# shematic.net
KiCad netlist of a schematic drawn in Altium Designer
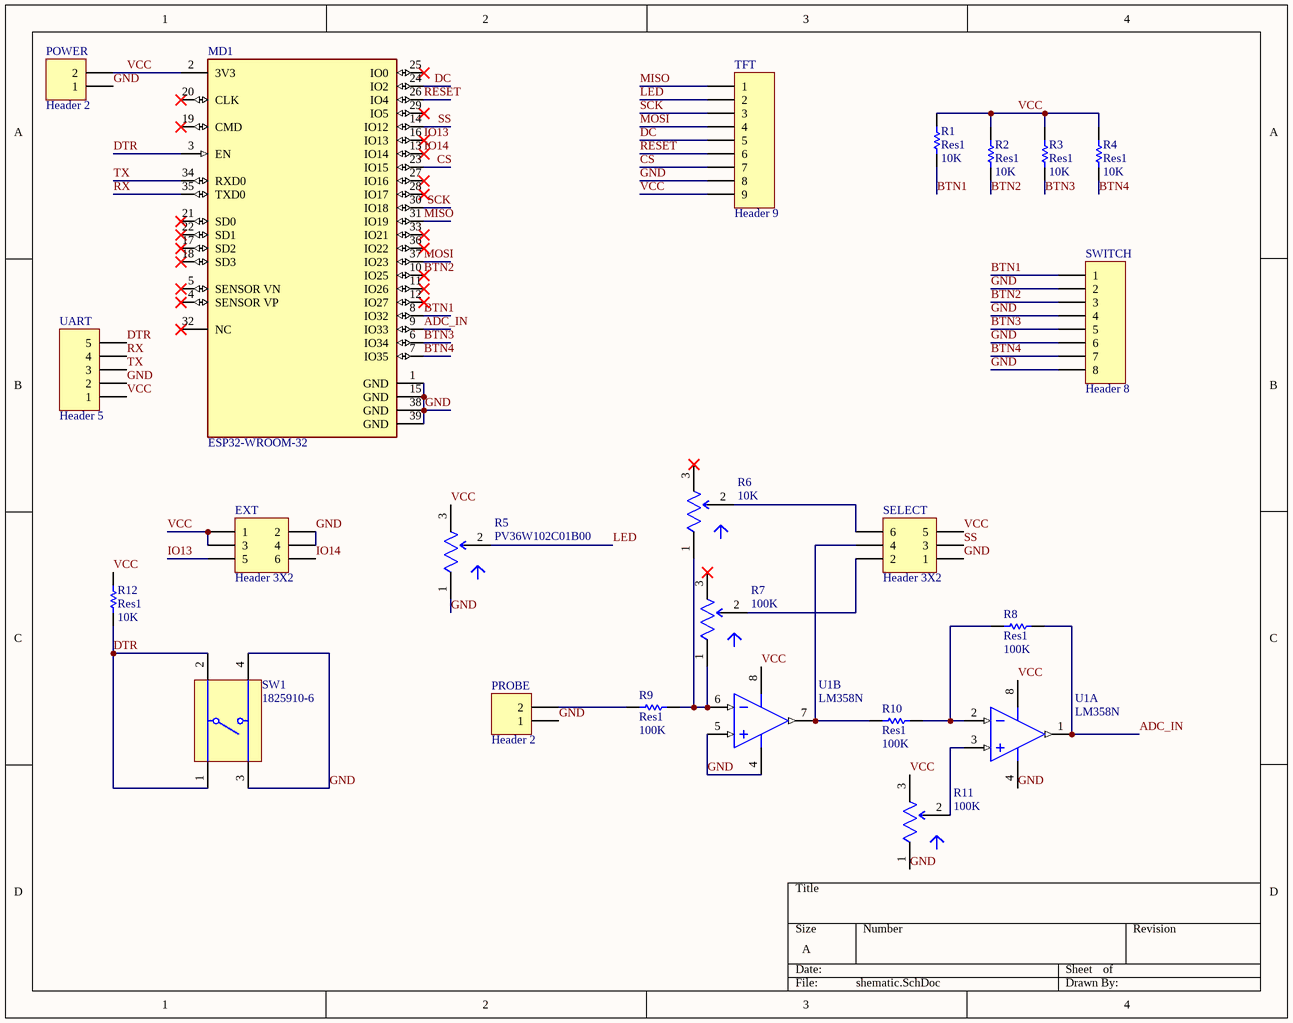
[diagram p0: shematic.SchDoc]

(export (version "E")
  (design (tool "Eeschema 10.0.6"))
  (components
    (comp (ref "EXT")
      (value "Header 3X2")
      (footprint "HDR2X3")
      (description "Header, 3-Pin, Dual row")
      (fields (field (name "PUBLISHER") "Altium Limited"))
      (libsource (lib "") (part "Header 3X2_1"))
    )
    (comp (ref "MD1")
      (value "ESP32-WROOM-32")
      (footprint "FP-ESP32-WROOM-32-MFG")
      (description "RX TXRX MOD WIFI SURFACE MOUNT")
      (libsource (lib "Altium Content Vault") (part "ee866abf0b6c51247b7f5cdebf2f250"))
    )
    (comp (ref "POWER")
      (value "Header 2")
      (footprint "HDR1X2")
      (description "Header, 2-Pin")
      (fields (field (name "PUBLISHER") "Altium Limited"))
      (libsource (lib "Miscellaneous Connectors") (part "Header 2"))
    )
    (comp (ref "PROBE")
      (value "Header 2")
      (footprint "HDR1X2")
      (description "Header, 2-Pin")
      (fields (field (name "PUBLISHER") "Altium Limited"))
      (libsource (lib "Miscellaneous Connectors") (part "Header 2"))
    )
    (comp (ref "R1")
      (value "Res1")
      (footprint "AXIAL-0.3")
      (description "Resistor")
      (fields (field (name "ALTIUM_VALUE") "10K") (field (name "PUBLISHER") "Altium Limited"))
      (libsource (lib "Miscellaneous Devices") (part "Res1"))
    )
    (comp (ref "R2")
      (value "Res1")
      (footprint "AXIAL-0.3")
      (description "Resistor")
      (fields (field (name "ALTIUM_VALUE") "10K") (field (name "PUBLISHER") "Altium Limited"))
      (libsource (lib "Miscellaneous Devices") (part "Res1"))
    )
    (comp (ref "R3")
      (value "Res1")
      (footprint "AXIAL-0.3")
      (description "Resistor")
      (fields (field (name "ALTIUM_VALUE") "10K") (field (name "PUBLISHER") "Altium Limited"))
      (libsource (lib "Miscellaneous Devices") (part "Res1"))
    )
    (comp (ref "R4")
      (value "Res1")
      (footprint "AXIAL-0.3")
      (description "Resistor")
      (fields (field (name "ALTIUM_VALUE") "10K") (field (name "PUBLISHER") "Altium Limited"))
      (libsource (lib "Miscellaneous Devices") (part "Res1"))
    )
    (comp (ref "R5")
      (value "PV36W102C01B00")
      (footprint "FP-PV36W-MFG")
      (description "TRIMMER 1K OHM 0.5W PC PIN TOP")
      (fields
        (field (name "OCTOPART") "https://octopart.com/pv36w102c01b00-bourns-71612321")
        (field (name "TOLERANCE") "10%")
      )
      (libsource (lib "Altium Content Vault") (part "3b5a993e1b8b55ba5d1e0805a406c64"))
    )
    (comp (ref "R6")
      (value "10K")
      (footprint "FP-PV36W-MFG")
      (description "TRIMMER 1K OHM 0.5W PC PIN TOP")
      (fields
        (field (name "OCTOPART") "https://octopart.com/pv36w102c01b00-bourns-71612321")
        (field (name "MANUFACTURER PART NUMBER") "PV36W102C01B00")
      )
      (libsource (lib "Altium Content Vault") (part "3b5a993e1b8b55ba5d1e0805a406c64"))
    )
    (comp (ref "R7")
      (value "100K")
      (footprint "FP-PV36W-MFG")
      (description "TRIMMER 1K OHM 0.5W PC PIN TOP")
      (fields
        (field (name "OCTOPART") "https://octopart.com/pv36w102c01b00-bourns-71612321")
        (field (name "MANUFACTURER PART NUMBER") "PV36W102C01B00")
      )
      (libsource (lib "Altium Content Vault") (part "3b5a993e1b8b55ba5d1e0805a406c64"))
    )
    (comp (ref "R8")
      (value "Res1")
      (footprint "AXIAL-0.3")
      (description "Resistor")
      (fields (field (name "ALTIUM_VALUE") "100K") (field (name "PUBLISHER") "Altium Limited"))
      (libsource (lib "Miscellaneous Devices") (part "Res1"))
    )
    (comp (ref "R9")
      (value "Res1")
      (footprint "AXIAL-0.3")
      (description "Resistor")
      (fields (field (name "ALTIUM_VALUE") "100K") (field (name "PUBLISHER") "Altium Limited"))
      (libsource (lib "Miscellaneous Devices") (part "Res1"))
    )
    (comp (ref "R10")
      (value "Res1")
      (footprint "AXIAL-0.3")
      (description "Resistor")
      (fields (field (name "ALTIUM_VALUE") "100K") (field (name "PUBLISHER") "Altium Limited"))
      (libsource (lib "Miscellaneous Devices") (part "Res1"))
    )
    (comp (ref "R11")
      (value "100K")
      (footprint "FP-PV36W-MFG")
      (description "TRIMMER 1K OHM 0.5W PC PIN TOP")
      (fields
        (field (name "OCTOPART") "https://octopart.com/pv36w102c01b00-bourns-71612321")
        (field (name "MANUFACTURER PART NUMBER") "PV36W102C01B00")
      )
      (libsource (lib "Altium Content Vault") (part "3b5a993e1b8b55ba5d1e0805a406c64"))
    )
    (comp (ref "R12")
      (value "Res1")
      (footprint "AXIAL-0.3")
      (description "Resistor")
      (fields (field (name "ALTIUM_VALUE") "10K") (field (name "PUBLISHER") "Altium Limited"))
      (libsource (lib "Miscellaneous Devices") (part "Res1"))
    )
    (comp (ref "SELECT")
      (value "Header 3X2")
      (footprint "HDR2X3")
      (description "Header, 3-Pin, Dual row")
      (fields (field (name "PUBLISHER") "Altium Limited"))
      (libsource (lib "Miscellaneous Connectors") (part "Header 3X2"))
    )
    (comp (ref "SW1")
      (value "1825910-6")
      (footprint "TECO-1825910-6_V")
      (description "Tact Switch, SPST-NO, 0.05 A, -35 to 85 degC, 4-Pin THD, RoHS, Bulk")
      (fields (field (name "MANUFACTURER") "TE Connectivity"))
      (libsource (lib "Altium Content Vault") (part "SW-SPST-4_A"))
    )
    (comp (ref "SWITCH")
      (value "Header 8")
      (footprint "HDR1X8")
      (description "Header, 8-Pin")
      (fields (field (name "PUBLISHER") "Altium Limited"))
      (libsource (lib "Miscellaneous Connectors") (part "Header 8"))
    )
    (comp (ref "TFT")
      (value "Header 9")
      (footprint "HDR1X9")
      (description "Header, 9-Pin")
      (fields (field (name "PUBLISHER") "Altium Limited"))
      (libsource (lib "Miscellaneous Connectors") (part "Header 9"))
    )
    (comp (ref "U1")
      (value "LM358N")
      (footprint "ONSC-PDIP-8-626-05_M")
      (description "Single Supply Dual Operational Amplifier, 3 to 32 V, 0 to 70 degC, 8-Pin PDIP, Tube")
      (fields (field (name "MANUFACTURER") "On Semiconductor"))
      (libsource (lib "Altium Content Vault") (part "ONSC-LM358_NCV2904-8"))
    )
    (comp (ref "UART")
      (value "Header 5")
      (footprint "HDR1X5")
      (description "Header, 5-Pin")
      (fields (field (name "PUBLISHER") "Altium Limited"))
      (libsource (lib "Miscellaneous Connectors") (part "Header 5"))
    )
  )
  (nets
    (net (code "1") (name "/ADC_IN") (class "Default")
      (node (ref "MD1") (pin "9") (pinfunction "IO33_9") (pintype "bidirectional"))
      (node (ref "R8") (pin "1") (pinfunction "1_1") (pintype "passive"))
      (node (ref "U1") (pin "1") (pinfunction "OUTA_1") (pintype "output"))
    )
    (net (code "2") (name "/BTN1") (class "Default")
      (node (ref "MD1") (pin "8") (pinfunction "IO32_8") (pintype "bidirectional"))
      (node (ref "R1") (pin "1") (pinfunction "1_1") (pintype "passive"))
      (node (ref "SWITCH") (pin "1") (pinfunction "1_1") (pintype "passive"))
    )
    (net (code "3") (name "/BTN2") (class "Default")
      (node (ref "MD1") (pin "10") (pinfunction "IO25_10") (pintype "bidirectional"))
      (node (ref "R2") (pin "1") (pinfunction "1_1") (pintype "passive"))
      (node (ref "SWITCH") (pin "3") (pinfunction "3_3") (pintype "passive"))
    )
    (net (code "4") (name "/BTN3") (class "Default")
      (node (ref "MD1") (pin "6") (pinfunction "IO34_6") (pintype "bidirectional"))
      (node (ref "R3") (pin "1") (pinfunction "1_1") (pintype "passive"))
      (node (ref "SWITCH") (pin "5") (pinfunction "5_5") (pintype "passive"))
    )
    (net (code "5") (name "/BTN4") (class "Default")
      (node (ref "MD1") (pin "7") (pinfunction "IO35_7") (pintype "bidirectional"))
      (node (ref "R4") (pin "1") (pinfunction "1_1") (pintype "passive"))
      (node (ref "SWITCH") (pin "7") (pinfunction "7_7") (pintype "passive"))
    )
    (net (code "6") (name "/CS") (class "Default")
      (node (ref "MD1") (pin "23") (pinfunction "IO15_23") (pintype "bidirectional"))
      (node (ref "TFT") (pin "7") (pinfunction "7_7") (pintype "passive"))
    )
    (net (code "7") (name "/DC") (class "Default")
      (node (ref "MD1") (pin "24") (pinfunction "IO2_24") (pintype "bidirectional"))
      (node (ref "TFT") (pin "5") (pinfunction "5_5") (pintype "passive"))
    )
    (net (code "8") (name "/DTR") (class "Default")
      (node (ref "MD1") (pin "3") (pinfunction "EN_3") (pintype "input"))
      (node (ref "R12") (pin "2") (pinfunction "2_2") (pintype "passive"))
      (node (ref "SW1") (pin "1") (pinfunction "1_1") (pintype "passive"))
      (node (ref "SW1") (pin "2") (pinfunction "2_2") (pintype "passive"))
      (node (ref "UART") (pin "5") (pinfunction "5_5") (pintype "passive"))
    )
    (net (code "9") (name "/GND") (class "Default")
      (node (ref "EXT") (pin "2") (pinfunction "2_2") (pintype "passive"))
      (node (ref "EXT") (pin "4") (pinfunction "4_4") (pintype "passive"))
      (node (ref "MD1") (pin "1") (pinfunction "GND_1") (pintype "power_in"))
      (node (ref "MD1") (pin "15") (pinfunction "GND_15") (pintype "power_in"))
      (node (ref "MD1") (pin "38") (pinfunction "GND_38") (pintype "power_in"))
      (node (ref "MD1") (pin "39") (pinfunction "GND_39") (pintype "power_in"))
      (node (ref "POWER") (pin "1") (pinfunction "1_1") (pintype "passive"))
      (node (ref "PROBE") (pin "1") (pinfunction "1_1") (pintype "passive"))
      (node (ref "R11") (pin "1") (pinfunction "1_1") (pintype "passive"))
      (node (ref "R5") (pin "1") (pinfunction "1_1") (pintype "passive"))
      (node (ref "SELECT") (pin "1") (pinfunction "1_1") (pintype "passive"))
      (node (ref "SW1") (pin "3") (pinfunction "3_3") (pintype "passive"))
      (node (ref "SW1") (pin "4") (pinfunction "4_4") (pintype "passive"))
      (node (ref "SWITCH") (pin "2") (pinfunction "2_2") (pintype "passive"))
      (node (ref "SWITCH") (pin "4") (pinfunction "4_4") (pintype "passive"))
      (node (ref "SWITCH") (pin "6") (pinfunction "6_6") (pintype "passive"))
      (node (ref "SWITCH") (pin "8") (pinfunction "8_8") (pintype "passive"))
      (node (ref "TFT") (pin "8") (pinfunction "8_8") (pintype "passive"))
      (node (ref "U1") (pin "4") (pinfunction "VEE/GND_4") (pintype "power_in"))
      (node (ref "U1") (pin "5") (pinfunction "INB+_5") (pintype "input"))
      (node (ref "UART") (pin "2") (pinfunction "2_2") (pintype "passive"))
    )
    (net (code "10") (name "/IO13") (class "Default")
      (node (ref "EXT") (pin "5") (pinfunction "5_5") (pintype "passive"))
      (node (ref "MD1") (pin "16") (pinfunction "IO13_16") (pintype "bidirectional"))
    )
    (net (code "11") (name "/IO14") (class "Default")
      (node (ref "EXT") (pin "6") (pinfunction "6_6") (pintype "passive"))
      (node (ref "MD1") (pin "13") (pinfunction "IO14_13") (pintype "bidirectional"))
    )
    (net (code "12") (name "/LED") (class "Default")
      (node (ref "R5") (pin "2") (pinfunction "Wiper_2") (pintype "passive"))
      (node (ref "TFT") (pin "2") (pinfunction "2_2") (pintype "passive"))
    )
    (net (code "13") (name "/MISO") (class "Default")
      (node (ref "MD1") (pin "31") (pinfunction "IO19_31") (pintype "bidirectional"))
      (node (ref "TFT") (pin "1") (pinfunction "1_1") (pintype "passive"))
    )
    (net (code "14") (name "/MOSI") (class "Default")
      (node (ref "MD1") (pin "37") (pinfunction "IO23_37") (pintype "bidirectional"))
      (node (ref "TFT") (pin "4") (pinfunction "4_4") (pintype "passive"))
    )
    (net (code "15") (name "/RESET") (class "Default")
      (node (ref "MD1") (pin "26") (pinfunction "IO4_26") (pintype "bidirectional"))
      (node (ref "TFT") (pin "6") (pinfunction "6_6") (pintype "passive"))
    )
    (net (code "16") (name "/RX") (class "Default")
      (node (ref "MD1") (pin "35") (pinfunction "TXD0_35") (pintype "bidirectional"))
      (node (ref "UART") (pin "4") (pinfunction "4_4") (pintype "passive"))
    )
    (net (code "17") (name "/SCK") (class "Default")
      (node (ref "MD1") (pin "30") (pinfunction "IO18_30") (pintype "bidirectional"))
      (node (ref "TFT") (pin "3") (pinfunction "3_3") (pintype "passive"))
    )
    (net (code "18") (name "/SS") (class "Default")
      (node (ref "MD1") (pin "14") (pinfunction "IO12_14") (pintype "bidirectional"))
      (node (ref "SELECT") (pin "3") (pinfunction "3_3") (pintype "passive"))
    )
    (net (code "19") (name "/TX") (class "Default")
      (node (ref "MD1") (pin "34") (pinfunction "RXD0_34") (pintype "bidirectional"))
      (node (ref "UART") (pin "3") (pinfunction "3_3") (pintype "passive"))
    )
    (net (code "20") (name "/VCC") (class "Default")
      (node (ref "EXT") (pin "1") (pinfunction "1_1") (pintype "passive"))
      (node (ref "EXT") (pin "3") (pinfunction "3_3") (pintype "passive"))
      (node (ref "MD1") (pin "2") (pinfunction "3V3_2") (pintype "power_in"))
      (node (ref "POWER") (pin "2") (pinfunction "2_2") (pintype "passive"))
      (node (ref "R1") (pin "2") (pinfunction "2_2") (pintype "passive"))
      (node (ref "R11") (pin "3") (pinfunction "3_3") (pintype "passive"))
      (node (ref "R12") (pin "1") (pinfunction "1_1") (pintype "passive"))
      (node (ref "R2") (pin "2") (pinfunction "2_2") (pintype "passive"))
      (node (ref "R3") (pin "2") (pinfunction "2_2") (pintype "passive"))
      (node (ref "R4") (pin "2") (pinfunction "2_2") (pintype "passive"))
      (node (ref "R5") (pin "3") (pinfunction "3_3") (pintype "passive"))
      (node (ref "SELECT") (pin "5") (pinfunction "5_5") (pintype "passive"))
      (node (ref "TFT") (pin "9") (pinfunction "9_9") (pintype "passive"))
      (node (ref "U1") (pin "8") (pinfunction "VCC_8") (pintype "power_in"))
      (node (ref "UART") (pin "1") (pinfunction "1_1") (pintype "passive"))
    )
    (net (code "21") (name "Net-(PROBE-Pad2)") (class "Default")
      (node (ref "PROBE") (pin "2") (pinfunction "2_2") (pintype "passive"))
      (node (ref "R9") (pin "2") (pinfunction "2_2") (pintype "passive"))
    )
    (net (code "22") (name "Net-(R6-Wiper)") (class "Default")
      (node (ref "R6") (pin "2") (pinfunction "Wiper_2") (pintype "passive"))
      (node (ref "SELECT") (pin "6") (pinfunction "6_6") (pintype "passive"))
    )
    (net (code "23") (name "Net-(R7-Wiper)") (class "Default")
      (node (ref "R7") (pin "2") (pinfunction "Wiper_2") (pintype "passive"))
      (node (ref "SELECT") (pin "2") (pinfunction "2_2") (pintype "passive"))
    )
    (net (code "24") (name "Net-(R11-Wiper)") (class "Default")
      (node (ref "R11") (pin "2") (pinfunction "Wiper_2") (pintype "passive"))
      (node (ref "U1") (pin "3") (pinfunction "INA+_3") (pintype "input"))
    )
    (net (code "25") (name "Net-(U1A-INA-)") (class "Default")
      (node (ref "R10") (pin "1") (pinfunction "1_1") (pintype "passive"))
      (node (ref "R8") (pin "2") (pinfunction "2_2") (pintype "passive"))
      (node (ref "U1") (pin "2") (pinfunction "INA-_2") (pintype "input"))
    )
    (net (code "26") (name "Net-(U1B-INB-)") (class "Default")
      (node (ref "R6") (pin "1") (pinfunction "1_1") (pintype "passive"))
      (node (ref "R7") (pin "1") (pinfunction "1_1") (pintype "passive"))
      (node (ref "R9") (pin "1") (pinfunction "1_1") (pintype "passive"))
      (node (ref "U1") (pin "6") (pinfunction "INB-_6") (pintype "input"))
    )
    (net (code "27") (name "Net-(U1B-OUTB)") (class "Default")
      (node (ref "R10") (pin "2") (pinfunction "2_2") (pintype "passive"))
      (node (ref "SELECT") (pin "4") (pinfunction "4_4") (pintype "passive"))
      (node (ref "U1") (pin "7") (pinfunction "OUTB_7") (pintype "output"))
    )
    (net (code "28") (name "unconnected-(MD1-CLK-Pad20)") (class "Default")
      (node (ref "MD1") (pin "20") (pinfunction "CLK_20") (pintype "bidirectional+no_connect"))
    )
    (net (code "29") (name "unconnected-(MD1-CMD-Pad19)") (class "Default")
      (node (ref "MD1") (pin "19") (pinfunction "CMD_19") (pintype "bidirectional+no_connect"))
    )
    (net (code "30") (name "unconnected-(MD1-IO0-Pad25)") (class "Default")
      (node (ref "MD1") (pin "25") (pinfunction "IO0_25") (pintype "bidirectional+no_connect"))
    )
    (net (code "31") (name "unconnected-(MD1-IO5-Pad29)") (class "Default")
      (node (ref "MD1") (pin "29") (pinfunction "IO5_29") (pintype "bidirectional+no_connect"))
    )
    (net (code "32") (name "unconnected-(MD1-IO16-Pad27)") (class "Default")
      (node (ref "MD1") (pin "27") (pinfunction "IO16_27") (pintype "bidirectional+no_connect"))
    )
    (net (code "33") (name "unconnected-(MD1-IO17-Pad28)") (class "Default")
      (node (ref "MD1") (pin "28") (pinfunction "IO17_28") (pintype "bidirectional+no_connect"))
    )
    (net (code "34") (name "unconnected-(MD1-IO21-Pad33)") (class "Default")
      (node (ref "MD1") (pin "33") (pinfunction "IO21_33") (pintype "bidirectional+no_connect"))
    )
    (net (code "35") (name "unconnected-(MD1-IO22-Pad36)") (class "Default")
      (node (ref "MD1") (pin "36") (pinfunction "IO22_36") (pintype "bidirectional+no_connect"))
    )
    (net (code "36") (name "unconnected-(MD1-IO26-Pad11)") (class "Default")
      (node (ref "MD1") (pin "11") (pinfunction "IO26_11") (pintype "bidirectional+no_connect"))
    )
    (net (code "37") (name "unconnected-(MD1-IO27-Pad12)") (class "Default")
      (node (ref "MD1") (pin "12") (pinfunction "IO27_12") (pintype "bidirectional+no_connect"))
    )
    (net (code "38") (name "unconnected-(MD1-NC-Pad32)") (class "Default")
      (node (ref "MD1") (pin "32") (pinfunction "NC_32") (pintype "passive+no_connect"))
    )
    (net (code "39") (name "unconnected-(MD1-SD0-Pad21)") (class "Default")
      (node (ref "MD1") (pin "21") (pinfunction "SD0_21") (pintype "bidirectional+no_connect"))
    )
    (net (code "40") (name "unconnected-(MD1-SD1-Pad22)") (class "Default")
      (node (ref "MD1") (pin "22") (pinfunction "SD1_22") (pintype "bidirectional+no_connect"))
    )
    (net (code "41") (name "unconnected-(MD1-SD2-Pad17)") (class "Default")
      (node (ref "MD1") (pin "17") (pinfunction "SD2_17") (pintype "bidirectional+no_connect"))
    )
    (net (code "42") (name "unconnected-(MD1-SD3-Pad18)") (class "Default")
      (node (ref "MD1") (pin "18") (pinfunction "SD3_18") (pintype "bidirectional+no_connect"))
    )
    (net (code "43") (name "unconnected-(MD1-SENSOR_VN-Pad5)") (class "Default")
      (node (ref "MD1") (pin "5") (pinfunction "SENSOR_VN_5") (pintype "bidirectional+no_connect"))
    )
    (net (code "44") (name "unconnected-(MD1-SENSOR_VP-Pad4)") (class "Default")
      (node (ref "MD1") (pin "4") (pinfunction "SENSOR_VP_4") (pintype "bidirectional+no_connect"))
    )
    (net (code "45") (name "unconnected-(R6-Pad3)") (class "Default")
      (node (ref "R6") (pin "3") (pinfunction "3_3") (pintype "passive+no_connect"))
    )
    (net (code "46") (name "unconnected-(R7-Pad3)") (class "Default")
      (node (ref "R7") (pin "3") (pinfunction "3_3") (pintype "passive+no_connect"))
    )
  )
)
